# RK3399_PMU.net
KiCad netlist of a schematic drawn in Altium Designer
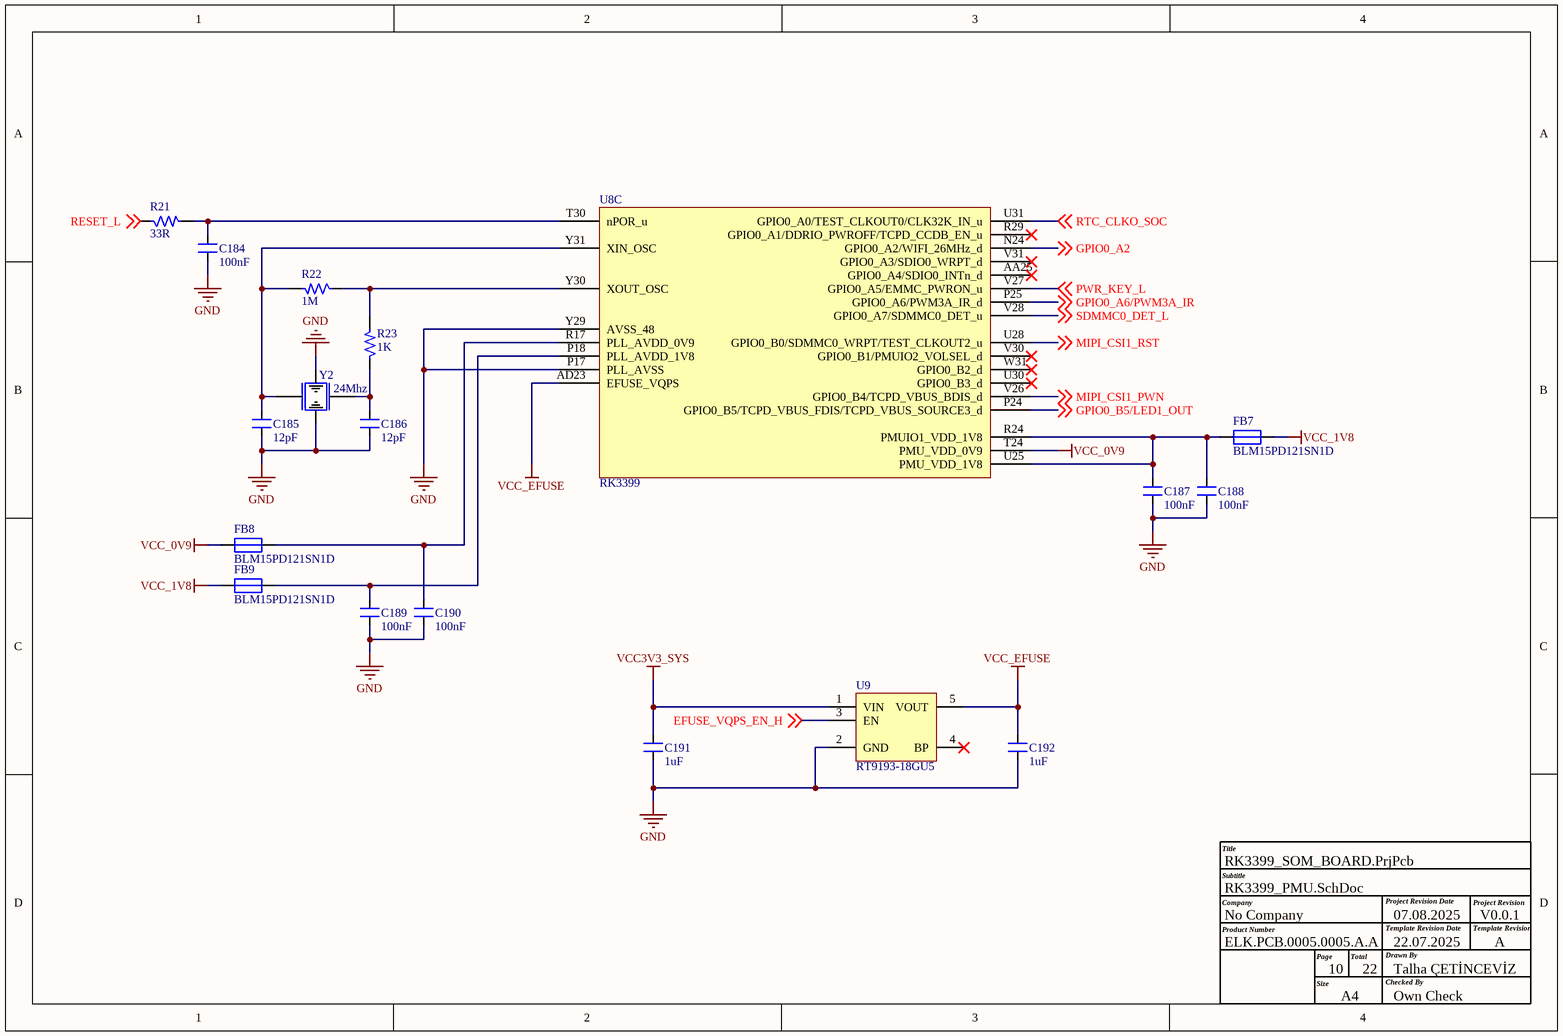
[diagram p0: RK3399_PMU.SchDoc]

(export (version "E")
  (design (tool "Eeschema 10.0.6"))
  (components
    (comp (ref "C184")
      (value "100nF")
      (footprint "CAP_0201")
      (description "0.1µF ±10% 25V Ceramic Capacitor X5R 0201 (0603 Metric)")
      (fields
        (field (name "MANUFACTURER") "TDK Corporation")
        (field (name "MANUFACTURER PART NUMBER") "C0603X5R1E104K030BB")
      )
      (libsource (lib "EsteemPCB_SOM_Course_intlib") (part "CAP_100nF-25V-10%-0201"))
    )
    (comp (ref "C185")
      (value "12pF")
      (footprint "CAP_0201")
      (description "12pF ±10% 16V Ceramic Capacitor C0G, NP0 0201 (0603 Metric)")
      (fields
        (field (name "MANUFACTURER") "AVX Corporation")
        (field (name "MANUFACTURER PART NUMBER") "0201YA120KAT2A")
      )
      (libsource (lib "EsteemPCB_SOM_Course_intlib") (part "CAP_12pF-16V-10%-0201"))
    )
    (comp (ref "C186")
      (value "12pF")
      (footprint "CAP_0201")
      (description "12pF ±10% 16V Ceramic Capacitor C0G, NP0 0201 (0603 Metric)")
      (fields
        (field (name "MANUFACTURER") "AVX Corporation")
        (field (name "MANUFACTURER PART NUMBER") "0201YA120KAT2A")
      )
      (libsource (lib "EsteemPCB_SOM_Course_intlib") (part "CAP_12pF-16V-10%-0201"))
    )
    (comp (ref "C187")
      (value "100nF")
      (footprint "CAP_0201")
      (description "0.1µF ±10% 25V Ceramic Capacitor X5R 0201 (0603 Metric)")
      (fields
        (field (name "MANUFACTURER") "TDK Corporation")
        (field (name "MANUFACTURER PART NUMBER") "C0603X5R1E104K030BB")
      )
      (libsource (lib "EsteemPCB_SOM_Course_intlib") (part "CAP_100nF-25V-10%-0201"))
    )
    (comp (ref "C188")
      (value "100nF")
      (footprint "CAP_0201")
      (description "0.1µF ±10% 25V Ceramic Capacitor X5R 0201 (0603 Metric)")
      (fields
        (field (name "MANUFACTURER") "TDK Corporation")
        (field (name "MANUFACTURER PART NUMBER") "C0603X5R1E104K030BB")
      )
      (libsource (lib "EsteemPCB_SOM_Course_intlib") (part "CAP_100nF-25V-10%-0201"))
    )
    (comp (ref "C189")
      (value "100nF")
      (footprint "CAP_0201")
      (description "0.1µF ±10% 25V Ceramic Capacitor X5R 0201 (0603 Metric)")
      (fields
        (field (name "MANUFACTURER") "TDK Corporation")
        (field (name "MANUFACTURER PART NUMBER") "C0603X5R1E104K030BB")
      )
      (libsource (lib "EsteemPCB_SOM_Course_intlib") (part "CAP_100nF-25V-10%-0201"))
    )
    (comp (ref "C190")
      (value "100nF")
      (footprint "CAP_0201")
      (description "0.1µF ±10% 25V Ceramic Capacitor X5R 0201 (0603 Metric)")
      (fields
        (field (name "MANUFACTURER") "TDK Corporation")
        (field (name "MANUFACTURER PART NUMBER") "C0603X5R1E104K030BB")
      )
      (libsource (lib "EsteemPCB_SOM_Course_intlib") (part "CAP_100nF-25V-10%-0201"))
    )
    (comp (ref "C191")
      (value "1uF")
      (footprint "CAP_0201")
      (description "1µF ±20% 16V Ceramic Capacitor X5R 0201 (0603 Metric)")
      (fields
        (field (name "MANUFACTURER") "Samsung Electro-Mechanics")
        (field (name "MANUFACTURER PART NUMBER") "CL03A105MO3NRNH")
      )
      (libsource (lib "EsteemPCB_SOM_Course_intlib") (part "CAP_1uF-16V-10%-0201"))
    )
    (comp (ref "C192")
      (value "1uF")
      (footprint "CAP_0201")
      (description "1µF ±20% 16V Ceramic Capacitor X5R 0201 (0603 Metric)")
      (fields
        (field (name "MANUFACTURER") "Samsung Electro-Mechanics")
        (field (name "MANUFACTURER PART NUMBER") "CL03A105MO3NRNH")
      )
      (libsource (lib "EsteemPCB_SOM_Course_intlib") (part "CAP_1uF-16V-10%-0201"))
    )
    (comp (ref "FB7")
      (value "BLM15PD121SN1D")
      (footprint "RES_0402")
      (description "120 Ohms @ 100MHz 1 Power Line Ferrite Bead 0402 (1005 Metric) 1.3A 90mOhm")
      (fields (field (name "MANUFACTURER") "Murata Electronics"))
      (libsource (lib "EsteemPCB_SOM_Course_intlib") (part "FB_120R-1.3A-100Mhz-0402"))
    )
    (comp (ref "FB8")
      (value "BLM15PD121SN1D")
      (footprint "RES_0402")
      (description "120 Ohms @ 100MHz 1 Power Line Ferrite Bead 0402 (1005 Metric) 1.3A 90mOhm")
      (fields (field (name "MANUFACTURER") "Murata Electronics"))
      (libsource (lib "EsteemPCB_SOM_Course_intlib") (part "FB_120R-1.3A-100Mhz-0402"))
    )
    (comp (ref "FB9")
      (value "BLM15PD121SN1D")
      (footprint "RES_0402")
      (description "120 Ohms @ 100MHz 1 Power Line Ferrite Bead 0402 (1005 Metric) 1.3A 90mOhm")
      (fields (field (name "MANUFACTURER") "Murata Electronics"))
      (libsource (lib "EsteemPCB_SOM_Course_intlib") (part "FB_120R-1.3A-100Mhz-0402"))
    )
    (comp (ref "R21")
      (value "33R")
      (footprint "RES_0201")
      (description "33 Ohms ±1% 0.05W, 1/20W Chip Resistor 0201 (0603 Metric) Thick Film")
      (fields
        (field (name "MANUFACTURER") "Yageo")
        (field (name "MANUFACTURER PART NUMBER") "RC0201FR-0733RL")
      )
      (libsource (lib "EsteemPCB_SOM_Course_intlib") (part "RES_33R-0.05W-1%-0201"))
    )
    (comp (ref "R22")
      (value "1M")
      (footprint "RES_0201")
      (description "1 MOhms ±1% 0.05W, 1/20W Chip Resistor 0201 (0603 Metric) Thick Film")
      (fields
        (field (name "MANUFACTURER") "Yageo")
        (field (name "MANUFACTURER PART NUMBER") "RC0201FR-071ML")
      )
      (libsource (lib "EsteemPCB_SOM_Course_intlib") (part "RES_1M-0.05W-1%-0201"))
    )
    (comp (ref "R23")
      (value "1K")
      (footprint "RES_0201")
      (description "1 kOhms ±1% 0.05W, 1/20W Chip Resistor 0201 (0603 Metric) Thick Film")
      (fields
        (field (name "MANUFACTURER") "Yageo")
        (field (name "MANUFACTURER PART NUMBER") "RC0201FR-071KL")
      )
      (libsource (lib "EsteemPCB_SOM_Course_intlib") (part "RES_1K-0.05W-1%-0201"))
    )
    (comp (ref "U8")
      (value "RK3399")
      (footprint "FBGA828_23_826X826")
      (description "RK3399 is a low power, high performance processor for computing, personal mobile.")
      (fields (field (name "MANUFACTURER") "Rockchip"))
      (libsource (lib "EsteemPCB_SOM_Course_intlib") (part "IC_RK3399-FCBGA828"))
    )
    (comp (ref "U9")
      (value "RT9193-18GU5")
      (footprint "SC70-5")
      (description "Linear Voltage Regulator IC 1 Output 300mA SC-70-5")
      (fields (field (name "MANUFACTURER") "Richtek USA Inc."))
      (libsource (lib "EsteemPCB_SOM_Course_intlib") (part "REG_1.8V-300mA-5.5V-SC70-5"))
    )
    (comp (ref "Y2")
      (value "24Mhz")
      (footprint "XTAL_ABM8AIG-24.000MHZ-12-2Z-T3")
      (description "24MHz ±20ppm Crystal 12pF 50 Ohms 4-SMD, No Lead")
      (fields
        (field (name "MANUFACTURER") "Abracon LLC")
        (field (name "MANUFACTURER PART NUMBER") "ABM8AIG-24.000MHZ-12-2Z-T3")
      )
      (libsource (lib "EsteemPCB_SOM_Course_intlib") (part "XTAL_24Mhz-12pF-4-SMD"))
    )
  )
  (nets
    (net (code "1") (name "EFUSE_VQPS_EN_H") (class "Default")
      (node (ref "U9") (pin "3") (pinfunction "EN_3") (pintype "passive"))
    )
    (net (code "2") (name "GND") (class "Default")
      (node (ref "C184") (pin "1") (pinfunction "1_1") (pintype "passive"))
      (node (ref "C185") (pin "1") (pinfunction "1_1") (pintype "passive"))
      (node (ref "C186") (pin "1") (pinfunction "1_1") (pintype "passive"))
      (node (ref "C187") (pin "1") (pinfunction "1_1") (pintype "passive"))
      (node (ref "C188") (pin "1") (pinfunction "1_1") (pintype "passive"))
      (node (ref "C189") (pin "1") (pinfunction "1_1") (pintype "passive"))
      (node (ref "C190") (pin "1") (pinfunction "1_1") (pintype "passive"))
      (node (ref "C191") (pin "1") (pinfunction "1_1") (pintype "passive"))
      (node (ref "C192") (pin "1") (pinfunction "1_1") (pintype "passive"))
      (node (ref "U8") (pin "P17") (pinfunction "PLL_AVSS_P17") (pintype "passive"))
      (node (ref "U8") (pin "Y29") (pinfunction "AVSS_48_Y29") (pintype "passive"))
      (node (ref "U9") (pin "2") (pinfunction "GND_2") (pintype "passive"))
      (node (ref "Y2") (pin "2") (pinfunction "2_2") (pintype "passive"))
      (node (ref "Y2") (pin "4") (pinfunction "4_4") (pintype "passive"))
    )
    (net (code "3") (name "GPIO0_A2") (class "Default")
      (node (ref "U8") (pin "N24") (pinfunction "GPIO0_A2/WIFI_26MHz_d_N24") (pintype "passive"))
    )
    (net (code "4") (name "GPIO0_A6{slash}PWM3A_IR") (class "Default")
      (node (ref "U8") (pin "P25") (pinfunction "GPIO0_A6/PWM3A_IR_d_P25") (pintype "passive"))
    )
    (net (code "5") (name "GPIO0_B5{slash}LED1_OUT") (class "Default")
      (node (ref "U8") (pin "P24") (pinfunction "GPIO0_B5/TCPD_VBUS_FDIS/TCPD_VBUS_SOURCE3_d_P24") (pintype "passive"))
    )
    (net (code "6") (name "MIPI_CSI1_PWN") (class "Default")
      (node (ref "U8") (pin "V26") (pinfunction "GPIO0_B4/TCPD_VBUS_BDIS_d_V26") (pintype "passive"))
    )
    (net (code "7") (name "MIPI_CSI1_RST") (class "Default")
      (node (ref "U8") (pin "U28") (pinfunction "GPIO0_B0/SDMMC0_WRPT/TEST_CLKOUT2_u_U28") (pintype "passive"))
    )
    (net (code "8") (name "Net-(C186-Pad2)") (class "Default")
      (node (ref "C186") (pin "2") (pinfunction "2_2") (pintype "passive"))
      (node (ref "R23") (pin "1") (pinfunction "1_1") (pintype "passive"))
      (node (ref "Y2") (pin "3") (pinfunction "3_3") (pintype "passive"))
    )
    (net (code "9") (name "Net-(U8C-PLL_AVDD_0V9)") (class "Default")
      (node (ref "C190") (pin "2") (pinfunction "2_2") (pintype "passive"))
      (node (ref "FB8") (pin "2") (pinfunction "2_2") (pintype "passive"))
      (node (ref "U8") (pin "R17") (pinfunction "PLL_AVDD_0V9_R17") (pintype "passive"))
    )
    (net (code "10") (name "Net-(U8C-PLL_AVDD_1V8)") (class "Default")
      (node (ref "C189") (pin "2") (pinfunction "2_2") (pintype "passive"))
      (node (ref "FB9") (pin "2") (pinfunction "2_2") (pintype "passive"))
      (node (ref "U8") (pin "P18") (pinfunction "PLL_AVDD_1V8_P18") (pintype "passive"))
    )
    (net (code "11") (name "Net-(U8C-PMUIO1_VDD_1V8)") (class "Default")
      (node (ref "C187") (pin "2") (pinfunction "2_2") (pintype "passive"))
      (node (ref "C188") (pin "2") (pinfunction "2_2") (pintype "passive"))
      (node (ref "FB7") (pin "1") (pinfunction "1_1") (pintype "passive"))
      (node (ref "U8") (pin "R24") (pinfunction "PMUIO1_VDD_1V8_R24") (pintype "passive"))
      (node (ref "U8") (pin "U25") (pinfunction "PMU_VDD_1V8_U25") (pintype "passive"))
    )
    (net (code "12") (name "Net-(U8C-XIN_OSC)") (class "Default")
      (node (ref "C185") (pin "2") (pinfunction "2_2") (pintype "passive"))
      (node (ref "R22") (pin "2") (pinfunction "2_2") (pintype "passive"))
      (node (ref "U8") (pin "Y31") (pinfunction "XIN_OSC_Y31") (pintype "passive"))
      (node (ref "Y2") (pin "1") (pinfunction "1_1") (pintype "passive"))
    )
    (net (code "13") (name "Net-(U8C-XOUT_OSC)") (class "Default")
      (node (ref "R22") (pin "1") (pinfunction "1_1") (pintype "passive"))
      (node (ref "R23") (pin "2") (pinfunction "2_2") (pintype "passive"))
      (node (ref "U8") (pin "Y30") (pinfunction "XOUT_OSC_Y30") (pintype "passive"))
    )
    (net (code "14") (name "Net-(U8C-nPOR_u)") (class "Default")
      (node (ref "C184") (pin "2") (pinfunction "2_2") (pintype "passive"))
      (node (ref "R21") (pin "2") (pinfunction "2_2") (pintype "passive"))
      (node (ref "U8") (pin "T30") (pinfunction "nPOR_u_T30") (pintype "passive"))
    )
    (net (code "15") (name "PWR_KEY_L") (class "Default")
      (node (ref "U8") (pin "V27") (pinfunction "GPIO0_A5/EMMC_PWRON_u_V27") (pintype "passive"))
    )
    (net (code "16") (name "RESET_L") (class "Default")
      (node (ref "R21") (pin "1") (pinfunction "1_1") (pintype "passive"))
    )
    (net (code "17") (name "RTC_CLKO_SOC") (class "Default")
      (node (ref "U8") (pin "U31") (pinfunction "GPIO0_A0/TEST_CLKOUT0/CLK32K_IN_u_U31") (pintype "passive"))
    )
    (net (code "18") (name "SDMMC0_DET_L") (class "Default")
      (node (ref "U8") (pin "V28") (pinfunction "GPIO0_A7/SDMMC0_DET_u_V28") (pintype "passive"))
    )
    (net (code "19") (name "VCC3V3_SYS") (class "Default")
      (node (ref "C191") (pin "2") (pinfunction "2_2") (pintype "passive"))
      (node (ref "U9") (pin "1") (pinfunction "VIN_1") (pintype "passive"))
    )
    (net (code "20") (name "VCC_0V9") (class "Default")
      (node (ref "FB8") (pin "1") (pinfunction "1_1") (pintype "passive"))
      (node (ref "U8") (pin "T24") (pinfunction "PMU_VDD_0V9_T24") (pintype "passive"))
    )
    (net (code "21") (name "VCC_1V8") (class "Default")
      (node (ref "FB7") (pin "2") (pinfunction "2_2") (pintype "passive"))
      (node (ref "FB9") (pin "1") (pinfunction "1_1") (pintype "passive"))
    )
    (net (code "22") (name "VCC_EFUSE") (class "Default")
      (node (ref "C192") (pin "2") (pinfunction "2_2") (pintype "passive"))
      (node (ref "U8") (pin "AD23") (pinfunction "EFUSE_VQPS_AD23") (pintype "passive"))
      (node (ref "U9") (pin "5") (pinfunction "VOUT_5") (pintype "passive"))
    )
    (net (code "23") (name "unconnected-(U8C-GPIO0_A1{slash}DDRIO_PWROFF{slash}TCPD_CCDB_EN_u-PadR29)") (class "Default")
      (node (ref "U8") (pin "R29") (pinfunction "GPIO0_A1/DDRIO_PWROFF/TCPD_CCDB_EN_u_R29") (pintype "passive+no_connect"))
    )
    (net (code "24") (name "unconnected-(U8C-GPIO0_A3{slash}SDIO0_WRPT_d-PadV31)") (class "Default")
      (node (ref "U8") (pin "V31") (pinfunction "GPIO0_A3/SDIO0_WRPT_d_V31") (pintype "passive+no_connect"))
    )
    (net (code "25") (name "unconnected-(U8C-GPIO0_A4{slash}SDIO0_INTn_d-PadAA25)") (class "Default")
      (node (ref "U8") (pin "AA25") (pinfunction "GPIO0_A4/SDIO0_INTn_d_AA25") (pintype "passive+no_connect"))
    )
    (net (code "26") (name "unconnected-(U8C-GPIO0_B1{slash}PMUIO2_VOLSEL_d-PadV30)") (class "Default")
      (node (ref "U8") (pin "V30") (pinfunction "GPIO0_B1/PMUIO2_VOLSEL_d_V30") (pintype "passive+no_connect"))
    )
    (net (code "27") (name "unconnected-(U8C-GPIO0_B2_d-PadW31)") (class "Default")
      (node (ref "U8") (pin "W31") (pinfunction "GPIO0_B2_d_W31") (pintype "passive+no_connect"))
    )
    (net (code "28") (name "unconnected-(U8C-GPIO0_B3_d-PadU30)") (class "Default")
      (node (ref "U8") (pin "U30") (pinfunction "GPIO0_B3_d_U30") (pintype "passive+no_connect"))
    )
    (net (code "29") (name "unconnected-(U9-BP-Pad4)") (class "Default")
      (node (ref "U9") (pin "4") (pinfunction "BP_4") (pintype "passive+no_connect"))
    )
  )
)
